# 02-100BASETX_PHY.net
KiCad netlist of a schematic drawn in Altium Designer
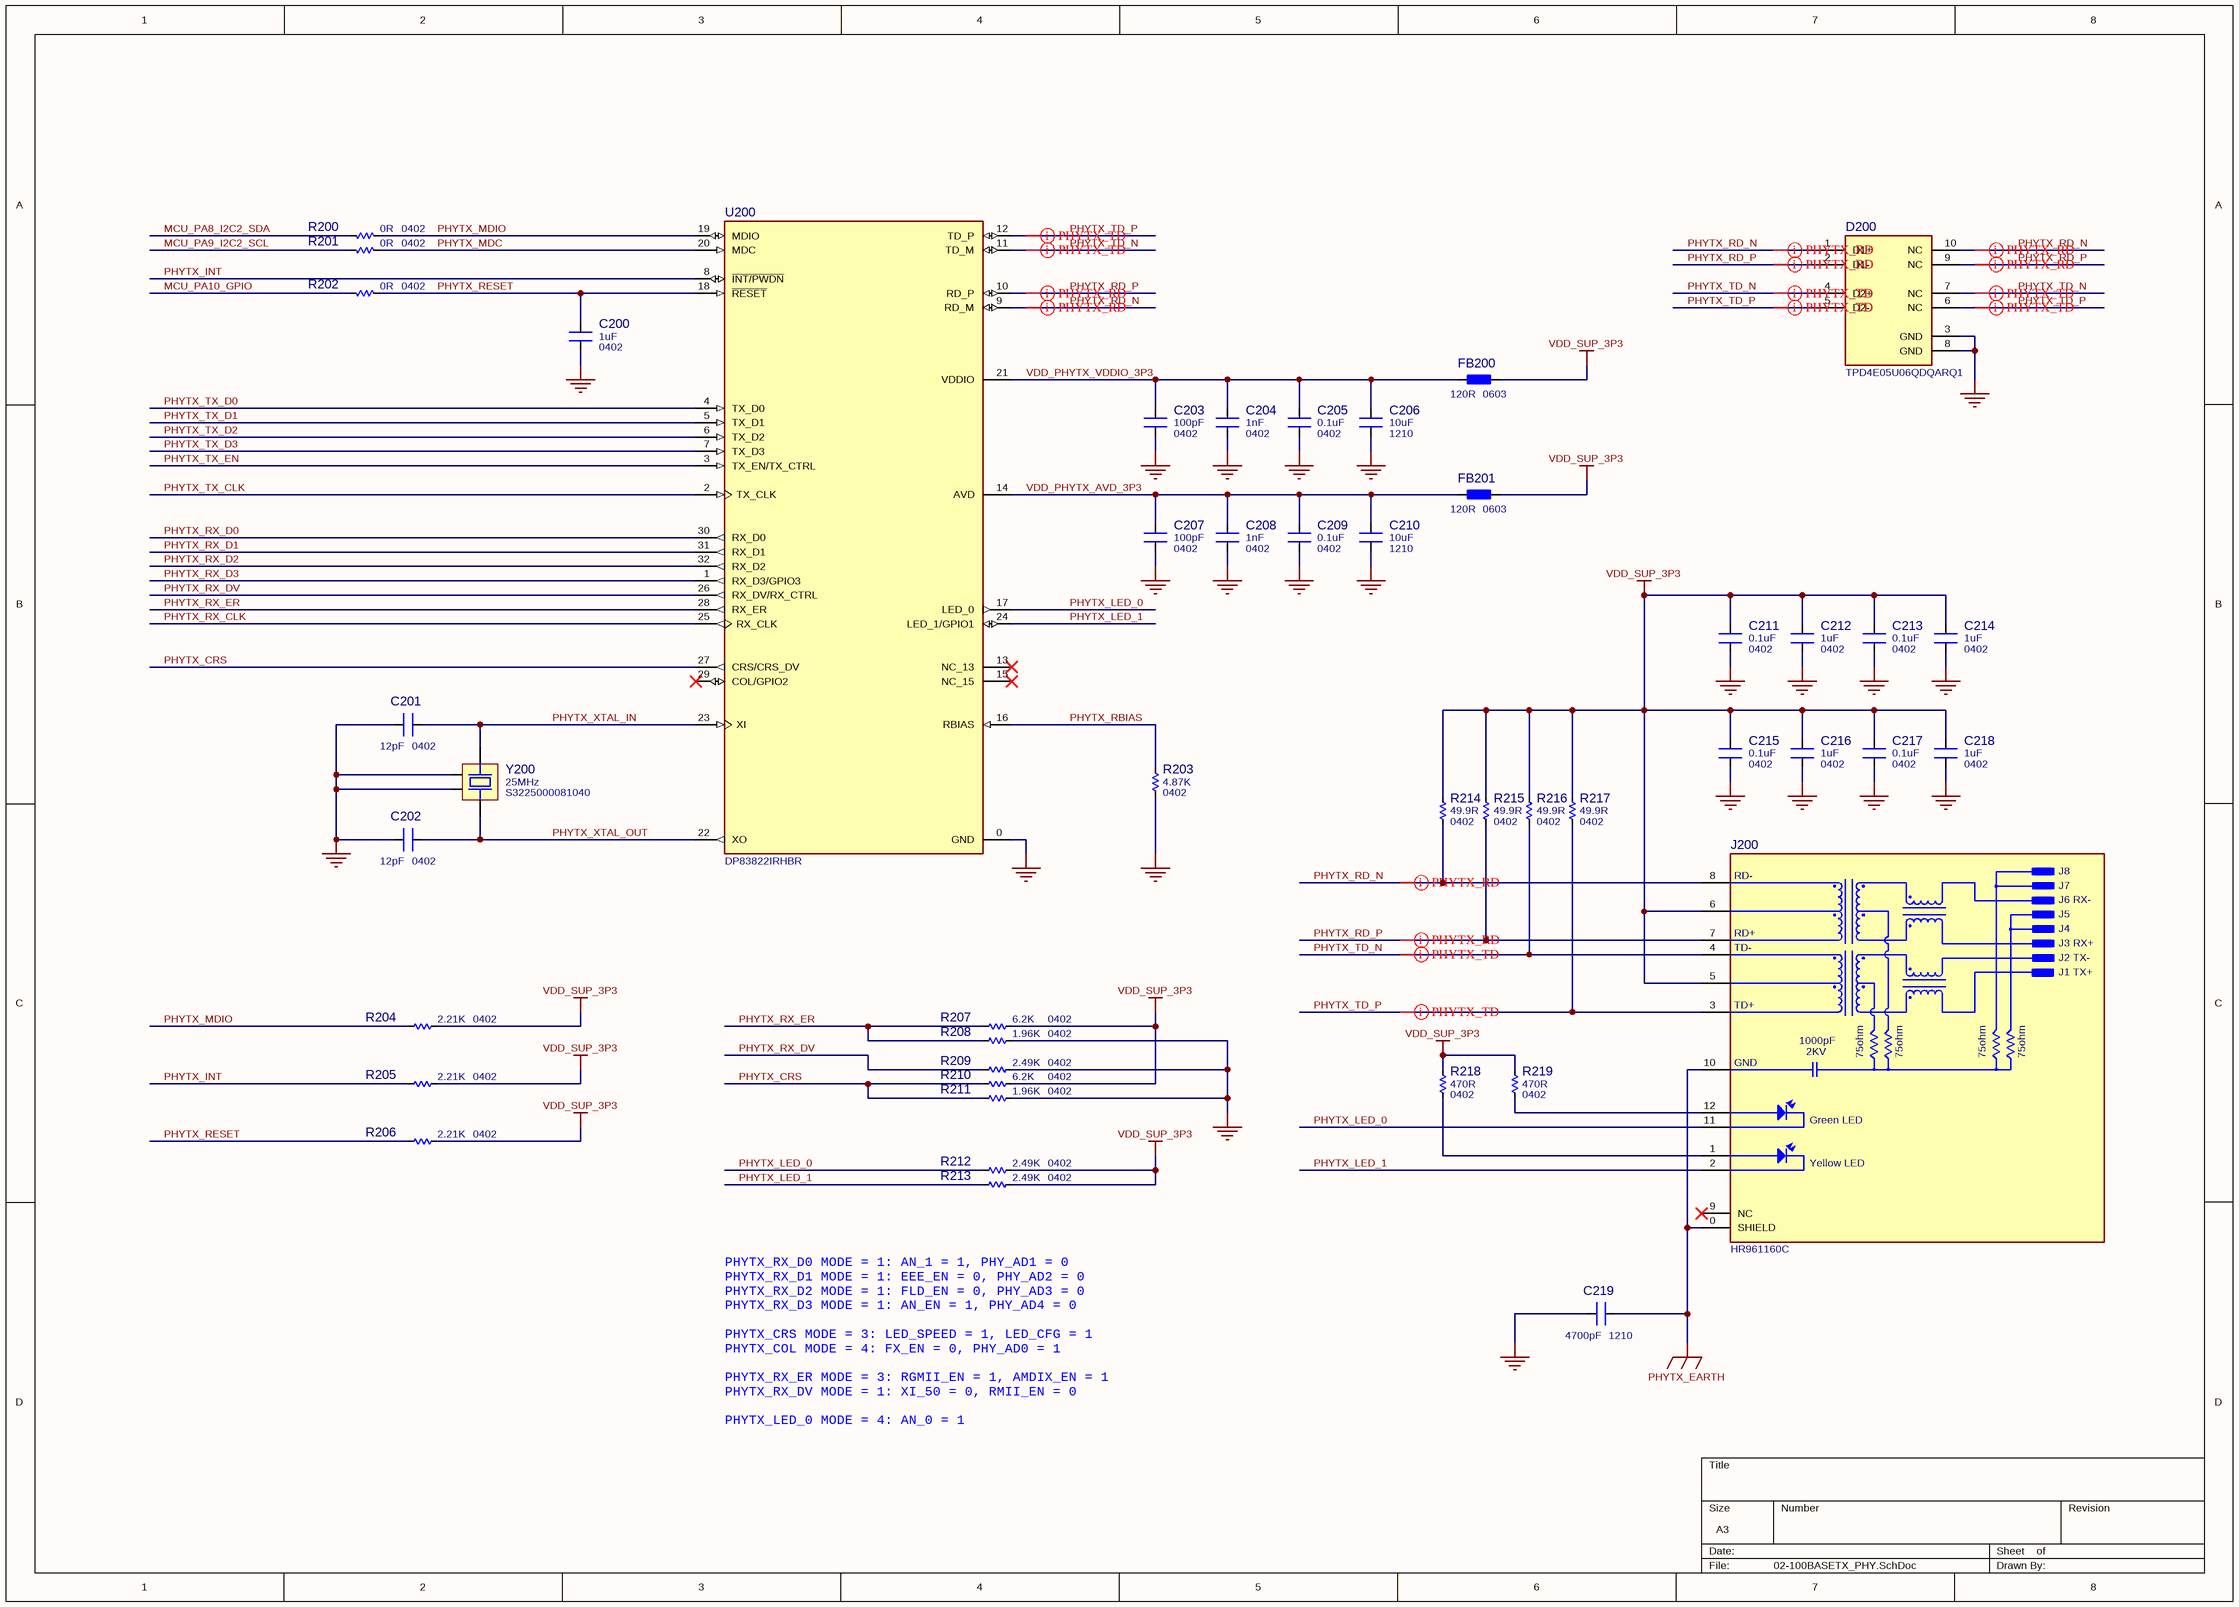
[diagram p0: 02-100BASETX_PHY.SchDoc]

(export (version "E")
  (design (tool "Eeschema 10.0.6"))
  (components
    (comp (ref "C200")
      (value "1uF")
      (footprint "CAP_C_0402")
      (description "Ceramic Capacitor SMD 0402 1uF ±10% 25V")
      (fields
        (field (name "TOLERANCE") "±10%")
        (field (name "MANUFACTURER") "Samsung")
        (field (name "PACKAGE") "0402")
      )
      (libsource (lib "AS50") (part "Cap"))
    )
    (comp (ref "C201")
      (value "12pF")
      (footprint "CAP_C_0402")
      (description "Ceramic Capacitor SMD 0402 12pF ±5% 50V")
      (fields
        (field (name "TOLERANCE") "±5%")
        (field (name "MANUFACTURER") "FH(Guangdong Fenghua Advanced Tech)")
        (field (name "PACKAGE") "0402")
      )
      (libsource (lib "AS50") (part "Cap"))
    )
    (comp (ref "C202")
      (value "12pF")
      (footprint "CAP_C_0402")
      (description "Ceramic Capacitor SMD 0402 12pF ±5% 50V")
      (fields
        (field (name "TOLERANCE") "±5%")
        (field (name "MANUFACTURER") "FH(Guangdong Fenghua Advanced Tech)")
        (field (name "PACKAGE") "0402")
      )
      (libsource (lib "AS50") (part "Cap"))
    )
    (comp (ref "C203")
      (value "100pF")
      (footprint "CAP_C_0402")
      (description "Ceramic Capacitor SMD 0402 100pF ±5% 50V")
      (fields
        (field (name "TOLERANCE") "±5%")
        (field (name "MANUFACTURER") "Samsung")
        (field (name "PACKAGE") "0402")
      )
      (libsource (lib "AS50") (part "Cap"))
    )
    (comp (ref "C204")
      (value "1nF")
      (footprint "CAP_C_0402")
      (description "Ceramic Capacitor SMD 0402 1nF ±10% 50V")
      (fields
        (field (name "TOLERANCE") "±10%")
        (field (name "MANUFACTURER") "Samsung")
        (field (name "PACKAGE") "0402")
      )
      (libsource (lib "AS50") (part "Cap"))
    )
    (comp (ref "C205")
      (value "0.1uF")
      (footprint "CAP_C_0402")
      (description "Ceramic Capacitor SMD 0402 100nF ±10% 16V")
      (fields
        (field (name "TOLERANCE") "±10%")
        (field (name "MANUFACTURER") "Samsung")
        (field (name "PACKAGE") "0402")
      )
      (libsource (lib "AS50") (part "Cap"))
    )
    (comp (ref "C206")
      (value "10uF")
      (footprint "CAP_C_1210")
      (description "Ceramic Capacitor SMD 1210 10uF ±10% 25V")
      (fields
        (field (name "TOLERANCE") "±10%")
        (field (name "MANUFACTURER") "Samsung")
        (field (name "PACKAGE") "1210")
      )
      (libsource (lib "AS50") (part "Cap"))
    )
    (comp (ref "C207")
      (value "100pF")
      (footprint "CAP_C_0402")
      (description "Ceramic Capacitor SMD 0402 100pF ±5% 50V")
      (fields
        (field (name "TOLERANCE") "±5%")
        (field (name "MANUFACTURER") "Samsung")
        (field (name "PACKAGE") "0402")
      )
      (libsource (lib "AS50") (part "Cap"))
    )
    (comp (ref "C208")
      (value "1nF")
      (footprint "CAP_C_0402")
      (description "Ceramic Capacitor SMD 0402 1nF ±10% 50V")
      (fields
        (field (name "TOLERANCE") "±10%")
        (field (name "MANUFACTURER") "Samsung")
        (field (name "PACKAGE") "0402")
      )
      (libsource (lib "AS50") (part "Cap"))
    )
    (comp (ref "C209")
      (value "0.1uF")
      (footprint "CAP_C_0402")
      (description "Ceramic Capacitor SMD 0402 100nF ±10% 16V")
      (fields
        (field (name "TOLERANCE") "±10%")
        (field (name "MANUFACTURER") "Samsung")
        (field (name "PACKAGE") "0402")
      )
      (libsource (lib "AS50") (part "Cap"))
    )
    (comp (ref "C210")
      (value "10uF")
      (footprint "CAP_C_1210")
      (description "Ceramic Capacitor SMD 1210 10uF ±10% 25V")
      (fields
        (field (name "TOLERANCE") "±10%")
        (field (name "MANUFACTURER") "Samsung")
        (field (name "PACKAGE") "1210")
      )
      (libsource (lib "AS50") (part "Cap"))
    )
    (comp (ref "C211")
      (value "0.1uF")
      (footprint "CAP_C_0402")
      (description "Ceramic Capacitor SMD 0402 100nF ±10% 16V")
      (fields
        (field (name "TOLERANCE") "±10%")
        (field (name "MANUFACTURER") "Samsung")
        (field (name "PACKAGE") "0402")
      )
      (libsource (lib "AS50") (part "Cap"))
    )
    (comp (ref "C212")
      (value "1uF")
      (footprint "CAP_C_0402")
      (description "Ceramic Capacitor SMD 0402 1uF ±10% 25V")
      (fields
        (field (name "TOLERANCE") "±10%")
        (field (name "MANUFACTURER") "Samsung")
        (field (name "PACKAGE") "0402")
      )
      (libsource (lib "AS50") (part "Cap"))
    )
    (comp (ref "C213")
      (value "0.1uF")
      (footprint "CAP_C_0402")
      (description "Ceramic Capacitor SMD 0402 100nF ±10% 16V")
      (fields
        (field (name "TOLERANCE") "±10%")
        (field (name "MANUFACTURER") "Samsung")
        (field (name "PACKAGE") "0402")
      )
      (libsource (lib "AS50") (part "Cap"))
    )
    (comp (ref "C214")
      (value "1uF")
      (footprint "CAP_C_0402")
      (description "Ceramic Capacitor SMD 0402 1uF ±10% 25V")
      (fields
        (field (name "TOLERANCE") "±10%")
        (field (name "MANUFACTURER") "Samsung")
        (field (name "PACKAGE") "0402")
      )
      (libsource (lib "AS50") (part "Cap"))
    )
    (comp (ref "C215")
      (value "0.1uF")
      (footprint "CAP_C_0402")
      (description "Ceramic Capacitor SMD 0402 100nF ±10% 16V")
      (fields
        (field (name "TOLERANCE") "±10%")
        (field (name "MANUFACTURER") "Samsung")
        (field (name "PACKAGE") "0402")
      )
      (libsource (lib "AS50") (part "Cap"))
    )
    (comp (ref "C216")
      (value "1uF")
      (footprint "CAP_C_0402")
      (description "Ceramic Capacitor SMD 0402 1uF ±10% 25V")
      (fields
        (field (name "TOLERANCE") "±10%")
        (field (name "MANUFACTURER") "Samsung")
        (field (name "PACKAGE") "0402")
      )
      (libsource (lib "AS50") (part "Cap"))
    )
    (comp (ref "C217")
      (value "0.1uF")
      (footprint "CAP_C_0402")
      (description "Ceramic Capacitor SMD 0402 100nF ±10% 16V")
      (fields
        (field (name "TOLERANCE") "±10%")
        (field (name "MANUFACTURER") "Samsung")
        (field (name "PACKAGE") "0402")
      )
      (libsource (lib "AS50") (part "Cap"))
    )
    (comp (ref "C218")
      (value "1uF")
      (footprint "CAP_C_0402")
      (description "Ceramic Capacitor SMD 0402 1uF ±10% 25V")
      (fields
        (field (name "TOLERANCE") "±10%")
        (field (name "MANUFACTURER") "Samsung")
        (field (name "PACKAGE") "0402")
      )
      (libsource (lib "AS50") (part "Cap"))
    )
    (comp (ref "C219")
      (value "4700pF")
      (footprint "CAP_C_1210")
      (description "Ceramic Capacitor SMD 1210 4700pF ±10% 2kV")
      (fields
        (field (name "TOLERANCE") "±10%")
        (field (name "MANUFACTURER") "KEMET")
        (field (name "PACKAGE") "1210")
      )
      (libsource (lib "AS50") (part "Cap"))
    )
    (comp (ref "D200")
      (value "TPDxE05U06-Q1")
      (footprint "SON50P100X250X55-10N")
      (description "Texas Instruments 1 and 4 Channel ESD Protection Diodes for SuperSpeed (Up to 6 Gbps) Interface")
      (fields
        (field (name "MANUFACTURER") "Texas Instruments")
        (field (name "MANUFACTURER PART NUMBER") "TPD4E05U06QDQARQ1")
      )
      (libsource (lib "AS50") (part "TPDxE05U06-Q1"))
    )
    (comp (ref "FB200")
      (value "120R")
      (footprint "Inductors:IND_C_0603")
      (description "Ferrite bead SMD 0603 120Ω ±25% @ 100MHz DCR=0.03Ω 3A")
      (fields
        (field (name "MANUFACTURER") "Murata Electronics")
        (field (name "MANUFACTURER PART NUMBER") "BLM18KG121TH1D")
        (field (name "PACKAGE") "0603")
      )
      (libsource (lib "AS50") (part "Ferrite bead"))
    )
    (comp (ref "FB201")
      (value "120R")
      (footprint "Inductors:IND_C_0603")
      (description "Ferrite bead SMD 0603 120Ω ±25% @ 100MHz DCR=0.03Ω 3A")
      (fields
        (field (name "MANUFACTURER") "Murata Electronics")
        (field (name "MANUFACTURER PART NUMBER") "BLM18KG121TH1D")
        (field (name "PACKAGE") "0603")
      )
      (libsource (lib "AS50") (part "Ferrite bead"))
    )
    (comp (ref "J200")
      (value "HR961160C")
      (footprint "RJ-45_HR961160C")
      (description "Single port RJ45 Connector with Integrated Magnetics and LED for 10/100-BaseTX NIC Applications")
      (fields (field (name "MANUFACTURER PART NUMBER") "HR961160C") (field (name "MANUFACTURER") "HanRun"))
      (libsource (lib "AS50") (part "HR961160C"))
    )
    (comp (ref "R200")
      (value "0R")
      (footprint "RES_C_0402")
      (description "Resistor SMD 0402 0R ±1% 1/16W")
      (fields (field (name "PACKAGE") "0402") (field (name "TOLERANCE") "±1%") (field (name "VOLTAGE") "50V"))
      (libsource (lib "AS50") (part "Res"))
    )
    (comp (ref "R201")
      (value "0R")
      (footprint "RES_C_0402")
      (description "Resistor SMD 0402 0R ±1% 1/16W")
      (fields (field (name "PACKAGE") "0402") (field (name "TOLERANCE") "±1%") (field (name "VOLTAGE") "50V"))
      (libsource (lib "AS50") (part "Res"))
    )
    (comp (ref "R202")
      (value "0R")
      (footprint "RES_C_0402")
      (description "Resistor SMD 0402 0R ±1% 1/16W")
      (fields (field (name "PACKAGE") "0402") (field (name "TOLERANCE") "±1%") (field (name "VOLTAGE") "50V"))
      (libsource (lib "AS50") (part "Res"))
    )
    (comp (ref "R203")
      (value "4.87K")
      (footprint "RES_C_0402")
      (description "Resistor SMD 0402 4.87K ±1% 1/16W")
      (fields (field (name "PACKAGE") "0402") (field (name "TOLERANCE") "±1%") (field (name "VOLTAGE") "50V"))
      (libsource (lib "AS50") (part "Res"))
    )
    (comp (ref "R204")
      (value "2.21K")
      (footprint "RES_C_0402")
      (description "Resistor SMD 0402 2.21K ±1% 1/16W")
      (fields (field (name "PACKAGE") "0402") (field (name "TOLERANCE") "±1%") (field (name "VOLTAGE") "50V"))
      (libsource (lib "AS50") (part "Res"))
    )
    (comp (ref "R205")
      (value "2.21K")
      (footprint "RES_C_0402")
      (description "Resistor SMD 0402 2.21K ±1% 1/16W")
      (fields (field (name "PACKAGE") "0402") (field (name "TOLERANCE") "±1%") (field (name "VOLTAGE") "50V"))
      (libsource (lib "AS50") (part "Res"))
    )
    (comp (ref "R206")
      (value "2.21K")
      (footprint "RES_C_0402")
      (description "Resistor SMD 0402 2.21K ±1% 1/16W")
      (fields (field (name "PACKAGE") "0402") (field (name "TOLERANCE") "±1%") (field (name "VOLTAGE") "50V"))
      (libsource (lib "AS50") (part "Res"))
    )
    (comp (ref "R207")
      (value "6.2K")
      (footprint "RES_C_0402")
      (description "Resistor SMD 0402 6.2K ±1% 1/16W")
      (fields (field (name "PACKAGE") "0402") (field (name "TOLERANCE") "±1%") (field (name "VOLTAGE") "50V"))
      (libsource (lib "AS50") (part "Res"))
    )
    (comp (ref "R208")
      (value "1.96K")
      (footprint "RES_C_0402")
      (description "Resistor SMD 0402 1.96K ±1% 1/16W")
      (fields (field (name "PACKAGE") "0402") (field (name "TOLERANCE") "±1%") (field (name "VOLTAGE") "50V"))
      (libsource (lib "AS50") (part "Res"))
    )
    (comp (ref "R209")
      (value "2.49K")
      (footprint "RES_C_0402")
      (description "Resistor SMD 0402 2.49K ±1% 1/16W")
      (fields (field (name "PACKAGE") "0402") (field (name "TOLERANCE") "±1%") (field (name "VOLTAGE") "50V"))
      (libsource (lib "AS50") (part "Res"))
    )
    (comp (ref "R210")
      (value "6.2K")
      (footprint "RES_C_0402")
      (description "Resistor SMD 0402 6.2K ±1% 1/16W")
      (fields (field (name "PACKAGE") "0402") (field (name "TOLERANCE") "±1%") (field (name "VOLTAGE") "50V"))
      (libsource (lib "AS50") (part "Res"))
    )
    (comp (ref "R211")
      (value "1.96K")
      (footprint "RES_C_0402")
      (description "Resistor SMD 0402 1.96K ±1% 1/16W")
      (fields (field (name "PACKAGE") "0402") (field (name "TOLERANCE") "±1%") (field (name "VOLTAGE") "50V"))
      (libsource (lib "AS50") (part "Res"))
    )
    (comp (ref "R212")
      (value "2.49K")
      (footprint "RES_C_0402")
      (description "Resistor SMD 0402 2.49K ±1% 1/16W")
      (fields (field (name "PACKAGE") "0402") (field (name "TOLERANCE") "±1%") (field (name "VOLTAGE") "50V"))
      (libsource (lib "AS50") (part "Res"))
    )
    (comp (ref "R213")
      (value "2.49K")
      (footprint "RES_C_0402")
      (description "Resistor SMD 0402 2.49K ±1% 1/16W")
      (fields (field (name "PACKAGE") "0402") (field (name "TOLERANCE") "±1%") (field (name "VOLTAGE") "50V"))
      (libsource (lib "AS50") (part "Res"))
    )
    (comp (ref "R214")
      (value "49.9R")
      (footprint "RES_C_0402")
      (description "Resistor SMD 0402 49.9R ±1% 1/16W")
      (fields (field (name "PACKAGE") "0402") (field (name "TOLERANCE") "±1%") (field (name "VOLTAGE") "50V"))
      (libsource (lib "AS50") (part "Res"))
    )
    (comp (ref "R215")
      (value "49.9R")
      (footprint "RES_C_0402")
      (description "Resistor SMD 0402 49.9R ±1% 1/16W")
      (fields (field (name "PACKAGE") "0402") (field (name "TOLERANCE") "±1%") (field (name "VOLTAGE") "50V"))
      (libsource (lib "AS50") (part "Res"))
    )
    (comp (ref "R216")
      (value "49.9R")
      (footprint "RES_C_0402")
      (description "Resistor SMD 0402 49.9R ±1% 1/16W")
      (fields (field (name "PACKAGE") "0402") (field (name "TOLERANCE") "±1%") (field (name "VOLTAGE") "50V"))
      (libsource (lib "AS50") (part "Res"))
    )
    (comp (ref "R217")
      (value "49.9R")
      (footprint "RES_C_0402")
      (description "Resistor SMD 0402 49.9R ±1% 1/16W")
      (fields (field (name "PACKAGE") "0402") (field (name "TOLERANCE") "±1%") (field (name "VOLTAGE") "50V"))
      (libsource (lib "AS50") (part "Res"))
    )
    (comp (ref "R218")
      (value "470R")
      (footprint "RES_C_0402")
      (description "Resistor SMD 0402 470R ±1% 1/16W")
      (fields (field (name "PACKAGE") "0402") (field (name "TOLERANCE") "±1%") (field (name "VOLTAGE") "50V"))
      (libsource (lib "AS50") (part "Res"))
    )
    (comp (ref "R219")
      (value "470R")
      (footprint "RES_C_0402")
      (description "Resistor SMD 0402 470R ±1% 1/16W")
      (fields (field (name "PACKAGE") "0402") (field (name "TOLERANCE") "±1%") (field (name "VOLTAGE") "50V"))
      (libsource (lib "AS50") (part "Res"))
    )
    (comp (ref "U200")
      (value "DP83822")
      (footprint "IC:QFN50P500X500X100_HS-33N")
      (description "Texas Instruments Low Power 10/100 Mbps Ethernet Physical Layer Transceiver")
      (fields
        (field (name "MANUFACTURER") "Texas Instruments")
        (field (name "MANUFACTURER PART NUMBER") "DP83822IRHBR")
      )
      (libsource (lib "AS50") (part "DP83822"))
    )
    (comp (ref "Y200")
      (value "Crystal")
      (footprint "XT-SMD-3225-4P")
      (description "25MHz SMD Crystal Resonator 8pF 40Ω ±10ppm -40℃~+85℃ SMD3225-4P")
      (fields
        (field (name "MANUFACTURER") "JGHC")
        (field (name "MANUFACTURER PART NUMBER") "S3225000081040")
        (field (name "FREQUENCY") "25MHz")
      )
      (libsource (lib "AS50") (part "CX3225SB12000H0PSTC1"))
    )
  )
  (nets
    (net (code "1") (name "/MCU_PA8_I2C2_SDA") (class "Default")
      (node (ref "R200") (pin "2") (pinfunction "2_2") (pintype "passive"))
    )
    (net (code "2") (name "/MCU_PA9_I2C2_SCL") (class "Default")
      (node (ref "R201") (pin "2") (pinfunction "2_2") (pintype "passive"))
    )
    (net (code "3") (name "/MCU_PA10_GPIO") (class "Default")
      (node (ref "R202") (pin "2") (pinfunction "2_2") (pintype "passive"))
    )
    (net (code "4") (name "/PHYTX_CRS") (class "Default")
      (node (ref "R210") (pin "1") (pinfunction "1_1") (pintype "passive"))
      (node (ref "R211") (pin "1") (pinfunction "1_1") (pintype "passive"))
      (node (ref "U200") (pin "27") (pinfunction "CRS/CRS_DV_27") (pintype "output"))
    )
    (net (code "5") (name "/PHYTX_INT") (class "Default")
      (node (ref "R205") (pin "1") (pinfunction "1_1") (pintype "passive"))
      (node (ref "U200") (pin "8") (pinfunction "~{INT/PWDN}_8") (pintype "bidirectional"))
    )
    (net (code "6") (name "/PHYTX_LED_0") (class "Default")
      (node (ref "J200") (pin "11") (pinfunction "GC_11") (pintype "passive"))
      (node (ref "R212") (pin "1") (pinfunction "1_1") (pintype "passive"))
      (node (ref "U200") (pin "17") (pinfunction "LED_0_17") (pintype "output"))
    )
    (net (code "7") (name "/PHYTX_LED_1") (class "Default")
      (node (ref "J200") (pin "2") (pinfunction "YC_2") (pintype "passive"))
      (node (ref "R213") (pin "1") (pinfunction "1_1") (pintype "passive"))
      (node (ref "U200") (pin "24") (pinfunction "LED_1/GPIO1_24") (pintype "bidirectional"))
    )
    (net (code "8") (name "/PHYTX_MDC") (class "Default")
      (node (ref "R201") (pin "1") (pinfunction "1_1") (pintype "passive"))
      (node (ref "U200") (pin "20") (pinfunction "MDC_20") (pintype "input"))
    )
    (net (code "9") (name "/PHYTX_MDIO") (class "Default")
      (node (ref "R200") (pin "1") (pinfunction "1_1") (pintype "passive"))
      (node (ref "R204") (pin "1") (pinfunction "1_1") (pintype "passive"))
      (node (ref "U200") (pin "19") (pinfunction "MDIO_19") (pintype "bidirectional"))
    )
    (net (code "10") (name "/PHYTX_RBIAS") (class "Default")
      (node (ref "R203") (pin "1") (pinfunction "1_1") (pintype "passive"))
      (node (ref "U200") (pin "16") (pinfunction "RBIAS_16") (pintype "input"))
    )
    (net (code "11") (name "/PHYTX_RD_N") (class "Default")
      (node (ref "D200") (pin "1") (pinfunction "D1+_1") (pintype "passive"))
      (node (ref "D200") (pin "10") (pinfunction "NC_10") (pintype "passive"))
      (node (ref "J200") (pin "8") (pinfunction "RD-_8") (pintype "passive"))
      (node (ref "R214") (pin "2") (pinfunction "2_2") (pintype "passive"))
      (node (ref "U200") (pin "9") (pinfunction "RD_M_9") (pintype "bidirectional"))
    )
    (net (code "12") (name "/PHYTX_RD_P") (class "Default")
      (node (ref "D200") (pin "2") (pinfunction "D1-_2") (pintype "passive"))
      (node (ref "D200") (pin "9") (pinfunction "NC_9") (pintype "passive"))
      (node (ref "J200") (pin "7") (pinfunction "RD+_7") (pintype "passive"))
      (node (ref "R215") (pin "2") (pinfunction "2_2") (pintype "passive"))
      (node (ref "U200") (pin "10") (pinfunction "RD_P_10") (pintype "bidirectional"))
    )
    (net (code "13") (name "/PHYTX_RESET") (class "Default")
      (node (ref "C200") (pin "2") (pinfunction "2_2") (pintype "passive"))
      (node (ref "R202") (pin "1") (pinfunction "1_1") (pintype "passive"))
      (node (ref "R206") (pin "1") (pinfunction "1_1") (pintype "passive"))
      (node (ref "U200") (pin "18") (pinfunction "~{RESET}_18") (pintype "input"))
    )
    (net (code "14") (name "/PHYTX_RX_CLK") (class "Default")
      (node (ref "U200") (pin "25") (pinfunction "RX_CLK_25") (pintype "output"))
    )
    (net (code "15") (name "/PHYTX_RX_D0") (class "Default")
      (node (ref "U200") (pin "30") (pinfunction "RX_D0_30") (pintype "output"))
    )
    (net (code "16") (name "/PHYTX_RX_D1") (class "Default")
      (node (ref "U200") (pin "31") (pinfunction "RX_D1_31") (pintype "output"))
    )
    (net (code "17") (name "/PHYTX_RX_D2") (class "Default")
      (node (ref "U200") (pin "32") (pinfunction "RX_D2_32") (pintype "output"))
    )
    (net (code "18") (name "/PHYTX_RX_D3") (class "Default")
      (node (ref "U200") (pin "1") (pinfunction "RX_D3/GPIO3_1") (pintype "output"))
    )
    (net (code "19") (name "/PHYTX_RX_DV") (class "Default")
      (node (ref "R209") (pin "1") (pinfunction "1_1") (pintype "passive"))
      (node (ref "U200") (pin "26") (pinfunction "RX_DV/RX_CTRL_26") (pintype "output"))
    )
    (net (code "20") (name "/PHYTX_RX_ER") (class "Default")
      (node (ref "R207") (pin "1") (pinfunction "1_1") (pintype "passive"))
      (node (ref "R208") (pin "1") (pinfunction "1_1") (pintype "passive"))
      (node (ref "U200") (pin "28") (pinfunction "RX_ER_28") (pintype "output"))
    )
    (net (code "21") (name "/PHYTX_TD_N") (class "Default")
      (node (ref "D200") (pin "4") (pinfunction "D2+_4") (pintype "passive"))
      (node (ref "D200") (pin "7") (pinfunction "NC_7") (pintype "passive"))
      (node (ref "J200") (pin "4") (pinfunction "TD-_4") (pintype "passive"))
      (node (ref "R216") (pin "2") (pinfunction "2_2") (pintype "passive"))
      (node (ref "U200") (pin "11") (pinfunction "TD_M_11") (pintype "bidirectional"))
    )
    (net (code "22") (name "/PHYTX_TD_P") (class "Default")
      (node (ref "D200") (pin "5") (pinfunction "D2-_5") (pintype "passive"))
      (node (ref "D200") (pin "6") (pinfunction "NC_6") (pintype "passive"))
      (node (ref "J200") (pin "3") (pinfunction "TD+_3") (pintype "passive"))
      (node (ref "R217") (pin "2") (pinfunction "2_2") (pintype "passive"))
      (node (ref "U200") (pin "12") (pinfunction "TD_P_12") (pintype "bidirectional"))
    )
    (net (code "23") (name "/PHYTX_TX_CLK") (class "Default")
      (node (ref "U200") (pin "2") (pinfunction "TX_CLK_2") (pintype "input"))
    )
    (net (code "24") (name "/PHYTX_TX_D0") (class "Default")
      (node (ref "U200") (pin "4") (pinfunction "TX_D0_4") (pintype "input"))
    )
    (net (code "25") (name "/PHYTX_TX_D1") (class "Default")
      (node (ref "U200") (pin "5") (pinfunction "TX_D1_5") (pintype "input"))
    )
    (net (code "26") (name "/PHYTX_TX_D2") (class "Default")
      (node (ref "U200") (pin "6") (pinfunction "TX_D2_6") (pintype "input"))
    )
    (net (code "27") (name "/PHYTX_TX_D3") (class "Default")
      (node (ref "U200") (pin "7") (pinfunction "TX_D3_7") (pintype "input"))
    )
    (net (code "28") (name "/PHYTX_TX_EN") (class "Default")
      (node (ref "U200") (pin "3") (pinfunction "TX_EN/TX_CTRL_3") (pintype "input"))
    )
    (net (code "29") (name "/PHYTX_XTAL_IN") (class "Default")
      (node (ref "C201") (pin "1") (pinfunction "1_1") (pintype "passive"))
      (node (ref "U200") (pin "23") (pinfunction "XI_23") (pintype "input"))
      (node (ref "Y200") (pin "1") (pinfunction "1_1") (pintype "passive"))
    )
    (net (code "30") (name "/PHYTX_XTAL_OUT") (class "Default")
      (node (ref "C202") (pin "1") (pinfunction "1_1") (pintype "passive"))
      (node (ref "U200") (pin "22") (pinfunction "XO_22") (pintype "output"))
      (node (ref "Y200") (pin "3") (pinfunction "3_3") (pintype "passive"))
    )
    (net (code "31") (name "/VDD_PHYTX_AVD_3P3") (class "Default")
      (node (ref "C207") (pin "2") (pinfunction "2_2") (pintype "passive"))
      (node (ref "C208") (pin "2") (pinfunction "2_2") (pintype "passive"))
      (node (ref "C209") (pin "2") (pinfunction "2_2") (pintype "passive"))
      (node (ref "C210") (pin "2") (pinfunction "2_2") (pintype "passive"))
      (node (ref "FB201") (pin "2") (pinfunction "2_2") (pintype "passive"))
      (node (ref "U200") (pin "14") (pinfunction "AVD_14") (pintype "power_in"))
    )
    (net (code "32") (name "/VDD_PHYTX_VDDIO_3P3") (class "Default")
      (node (ref "C203") (pin "2") (pinfunction "2_2") (pintype "passive"))
      (node (ref "C204") (pin "2") (pinfunction "2_2") (pintype "passive"))
      (node (ref "C205") (pin "2") (pinfunction "2_2") (pintype "passive"))
      (node (ref "C206") (pin "2") (pinfunction "2_2") (pintype "passive"))
      (node (ref "FB200") (pin "2") (pinfunction "2_2") (pintype "passive"))
      (node (ref "U200") (pin "21") (pinfunction "VDDIO_21") (pintype "power_in"))
    )
    (net (code "33") (name "GND") (class "Default")
      (node (ref "C200") (pin "1") (pinfunction "1_1") (pintype "passive"))
      (node (ref "C201") (pin "2") (pinfunction "2_2") (pintype "passive"))
      (node (ref "C202") (pin "2") (pinfunction "2_2") (pintype "passive"))
      (node (ref "C203") (pin "1") (pinfunction "1_1") (pintype "passive"))
      (node (ref "C204") (pin "1") (pinfunction "1_1") (pintype "passive"))
      (node (ref "C205") (pin "1") (pinfunction "1_1") (pintype "passive"))
      (node (ref "C206") (pin "1") (pinfunction "1_1") (pintype "passive"))
      (node (ref "C207") (pin "1") (pinfunction "1_1") (pintype "passive"))
      (node (ref "C208") (pin "1") (pinfunction "1_1") (pintype "passive"))
      (node (ref "C209") (pin "1") (pinfunction "1_1") (pintype "passive"))
      (node (ref "C210") (pin "1") (pinfunction "1_1") (pintype "passive"))
      (node (ref "C211") (pin "1") (pinfunction "1_1") (pintype "passive"))
      (node (ref "C212") (pin "1") (pinfunction "1_1") (pintype "passive"))
      (node (ref "C213") (pin "1") (pinfunction "1_1") (pintype "passive"))
      (node (ref "C214") (pin "1") (pinfunction "1_1") (pintype "passive"))
      (node (ref "C215") (pin "1") (pinfunction "1_1") (pintype "passive"))
      (node (ref "C216") (pin "1") (pinfunction "1_1") (pintype "passive"))
      (node (ref "C217") (pin "1") (pinfunction "1_1") (pintype "passive"))
      (node (ref "C218") (pin "1") (pinfunction "1_1") (pintype "passive"))
      (node (ref "C219") (pin "2") (pinfunction "2_2") (pintype "passive"))
      (node (ref "D200") (pin "3") (pinfunction "GND_3") (pintype "passive"))
      (node (ref "D200") (pin "8") (pinfunction "GND_8") (pintype "passive"))
      (node (ref "R203") (pin "2") (pinfunction "2_2") (pintype "passive"))
      (node (ref "R208") (pin "2") (pinfunction "2_2") (pintype "passive"))
      (node (ref "R209") (pin "2") (pinfunction "2_2") (pintype "passive"))
      (node (ref "R211") (pin "2") (pinfunction "2_2") (pintype "passive"))
      (node (ref "U200") (pin "0") (pinfunction "GND_0") (pintype "power_in"))
      (node (ref "Y200") (pin "2") (pinfunction "2_2") (pintype "power_in"))
      (node (ref "Y200") (pin "4") (pinfunction "4_4") (pintype "power_in"))
    )
    (net (code "34") (name "Net-(J200-GA)") (class "Default")
      (node (ref "J200") (pin "12") (pinfunction "GA_12") (pintype "passive"))
      (node (ref "R219") (pin "2") (pinfunction "2_2") (pintype "passive"))
    )
    (net (code "35") (name "Net-(J200-YA)") (class "Default")
      (node (ref "J200") (pin "1") (pinfunction "YA_1") (pintype "passive"))
      (node (ref "R218") (pin "2") (pinfunction "2_2") (pintype "passive"))
    )
    (net (code "36") (name "PHYTX_EARTH") (class "Default")
      (node (ref "C219") (pin "1") (pinfunction "1_1") (pintype "passive"))
      (node (ref "J200") (pin "0") (pinfunction "SHIELD_0") (pintype "passive"))
      (node (ref "J200") (pin "10") (pinfunction "GND_10") (pintype "power_in"))
    )
    (net (code "37") (name "VDD_SUP_3P3") (class "Default")
      (node (ref "C211") (pin "2") (pinfunction "2_2") (pintype "passive"))
      (node (ref "C212") (pin "2") (pinfunction "2_2") (pintype "passive"))
      (node (ref "C213") (pin "2") (pinfunction "2_2") (pintype "passive"))
      (node (ref "C214") (pin "2") (pinfunction "2_2") (pintype "passive"))
      (node (ref "C215") (pin "2") (pinfunction "2_2") (pintype "passive"))
      (node (ref "C216") (pin "2") (pinfunction "2_2") (pintype "passive"))
      (node (ref "C217") (pin "2") (pinfunction "2_2") (pintype "passive"))
      (node (ref "C218") (pin "2") (pinfunction "2_2") (pintype "passive"))
      (node (ref "FB200") (pin "1") (pinfunction "1_1") (pintype "passive"))
      (node (ref "FB201") (pin "1") (pinfunction "1_1") (pintype "passive"))
      (node (ref "J200") (pin "5") (pinfunction "P5_5") (pintype "passive"))
      (node (ref "J200") (pin "6") (pinfunction "P6_6") (pintype "passive"))
      (node (ref "R204") (pin "2") (pinfunction "2_2") (pintype "passive"))
      (node (ref "R205") (pin "2") (pinfunction "2_2") (pintype "passive"))
      (node (ref "R206") (pin "2") (pinfunction "2_2") (pintype "passive"))
      (node (ref "R207") (pin "2") (pinfunction "2_2") (pintype "passive"))
      (node (ref "R210") (pin "2") (pinfunction "2_2") (pintype "passive"))
      (node (ref "R212") (pin "2") (pinfunction "2_2") (pintype "passive"))
      (node (ref "R213") (pin "2") (pinfunction "2_2") (pintype "passive"))
      (node (ref "R214") (pin "1") (pinfunction "1_1") (pintype "passive"))
      (node (ref "R215") (pin "1") (pinfunction "1_1") (pintype "passive"))
      (node (ref "R216") (pin "1") (pinfunction "1_1") (pintype "passive"))
      (node (ref "R217") (pin "1") (pinfunction "1_1") (pintype "passive"))
      (node (ref "R218") (pin "1") (pinfunction "1_1") (pintype "passive"))
      (node (ref "R219") (pin "1") (pinfunction "1_1") (pintype "passive"))
    )
    (net (code "38") (name "unconnected-(J200-NC-Pad9)") (class "Default")
      (node (ref "J200") (pin "9") (pinfunction "NC_9") (pintype "passive+no_connect"))
    )
    (net (code "39") (name "unconnected-(U200-COL{slash}GPIO2-Pad29)") (class "Default")
      (node (ref "U200") (pin "29") (pinfunction "COL/GPIO2_29") (pintype "bidirectional+no_connect"))
    )
    (net (code "40") (name "unconnected-(U200-NC_13-Pad13)") (class "Default")
      (node (ref "U200") (pin "13") (pinfunction "NC_13_13") (pintype "passive+no_connect"))
    )
    (net (code "41") (name "unconnected-(U200-NC_15-Pad15)") (class "Default")
      (node (ref "U200") (pin "15") (pinfunction "NC_15_15") (pintype "passive+no_connect"))
    )
  )
)
